# ToolChestAutoLight.net
KiCad netlist of a schematic drawn in EAGLE
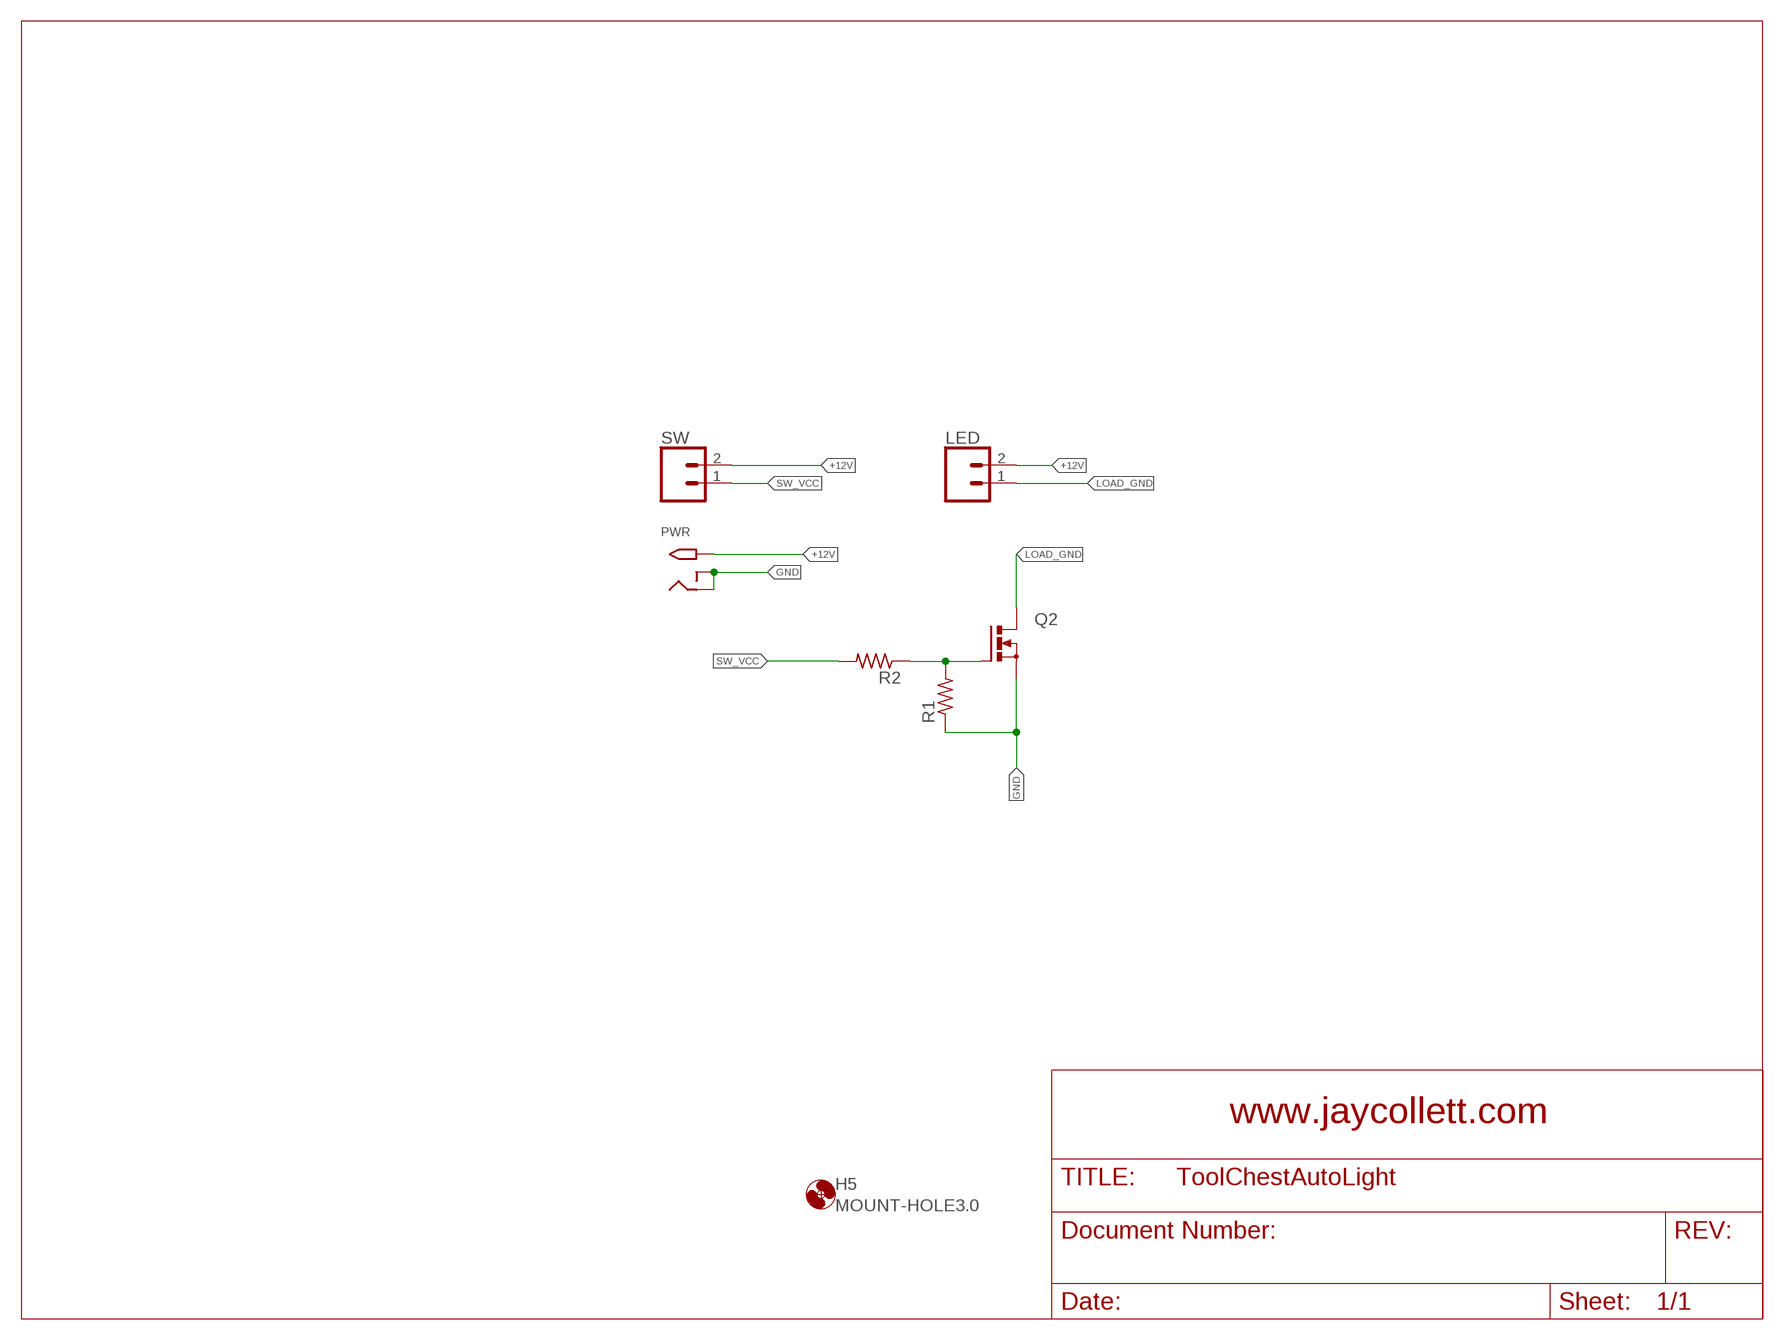
[diagram p0: schematic, sheet 1]

(export (version "E")
  (design (tool "Eeschema 10.0.6"))
  (components
    (comp (ref "H5")
      (value "MOUNT-HOLE3.0")
      (footprint "eagle-import:3,0")
      (libsource (lib "eagle-import") (part "MOUNT-HOLE3.0"))
    )
    (comp (ref "LED")
      (value "CONN_02LOCK_LONGPADS")
      (footprint "eagle-import:1X02_LOCK_LONGPADS")
      (libsource (lib "eagle-import") (part "CONN_02LOCK_LONGPADS"))
    )
    (comp (ref "PWR")
      (value "2.1MMJACKTHM")
      (footprint "eagle-import:PJ-102A")
      (libsource (lib "eagle-import") (part "2.1MMJACKTHM"))
    )
    (comp (ref "Q2")
      (value "PMOSFET_NTO220BH")
      (footprint "eagle-import:TO220BH")
      (libsource (lib "eagle-import") (part "PMOSFET_NTO220BH"))
    )
    (comp (ref "R1")
      (value "R-US_0204/5")
      (footprint "eagle-import:0204_5")
      (libsource (lib "eagle-import") (part "R-US_0204/5"))
    )
    (comp (ref "R2")
      (value "R-US_0204/5")
      (footprint "eagle-import:0204_5")
      (libsource (lib "eagle-import") (part "R-US_0204/5"))
    )
    (comp (ref "SW")
      (value "CONN_02LOCK_LONGPADS")
      (footprint "eagle-import:1X02_LOCK_LONGPADS")
      (libsource (lib "eagle-import") (part "CONN_02LOCK_LONGPADS"))
    )
  )
  (nets
    (net (code "1") (name "+12V") (class "Default")
      (node (ref "LED") (pin "2") (pinfunction "2_2") (pintype "passive"))
      (node (ref "PWR") (pin "TIP") (pinfunction "TIP_TIP") (pintype "bidirectional"))
      (node (ref "SW") (pin "2") (pinfunction "2_2") (pintype "passive"))
    )
    (net (code "2") (name "GND") (class "Default")
      (node (ref "PWR") (pin "RING") (pinfunction "RING_RING") (pintype "bidirectional"))
      (node (ref "PWR") (pin "RING_SW") (pinfunction "RING_SW_RING_SW") (pintype "bidirectional"))
      (node (ref "Q2") (pin "S") (pinfunction "S_S") (pintype "passive"))
      (node (ref "R1") (pin "1") (pinfunction "1_1") (pintype "passive"))
    )
    (net (code "3") (name "LOAD_GND") (class "Default")
      (node (ref "LED") (pin "1") (pinfunction "1_1") (pintype "passive"))
      (node (ref "Q2") (pin "D") (pinfunction "D_D") (pintype "passive"))
    )
    (net (code "4") (name "Net-(Q2-PadG)") (class "Default")
      (node (ref "Q2") (pin "G") (pinfunction "G_G") (pintype "passive"))
      (node (ref "R1") (pin "2") (pinfunction "2_2") (pintype "passive"))
      (node (ref "R2") (pin "1") (pinfunction "1_1") (pintype "passive"))
    )
    (net (code "5") (name "SW_VCC") (class "Default")
      (node (ref "R2") (pin "2") (pinfunction "2_2") (pintype "passive"))
      (node (ref "SW") (pin "1") (pinfunction "1_1") (pintype "passive"))
    )
  )
)
